# Jds-040-Usb-C.net
KiCad netlist of a schematic drawn in EAGLE
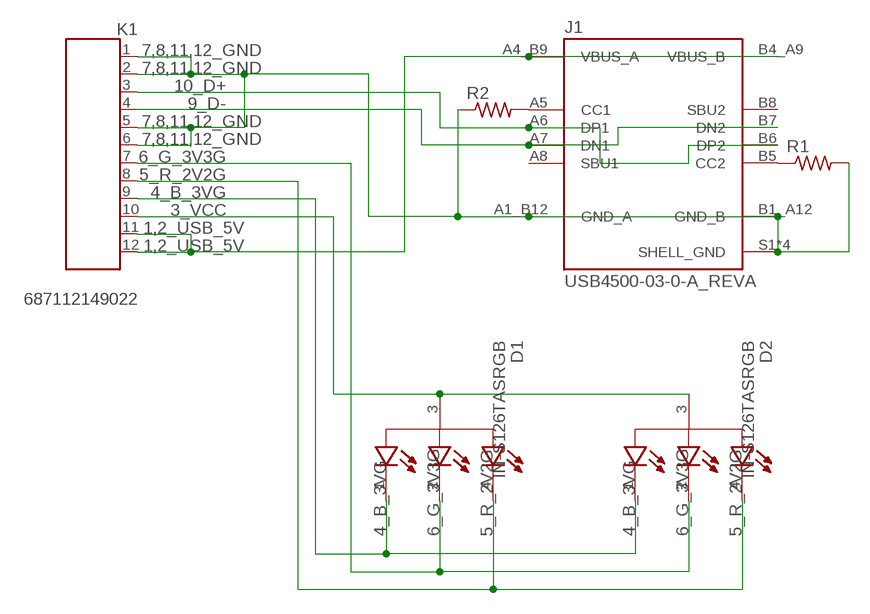
[diagram p0: schematic, sheet 1]

(export (version "E")
  (design (tool "Eeschema 10.0.6"))
  (components
    (comp (ref "D1")
      (value "IN-S126TASRGB")
      (footprint "eagle-import:LED_IN-S126TASRGB")
      (fields (field (name "MF") "Inolux"))
      (libsource (lib "eagle-import") (part "IN-S126TASRGB"))
    )
    (comp (ref "D2")
      (value "IN-S126TASRGB")
      (footprint "eagle-import:LED_IN-S126TASRGB")
      (fields (field (name "MF") "Inolux"))
      (libsource (lib "eagle-import") (part "IN-S126TASRGB"))
    )
    (comp (ref "J1")
      (value "USB4500-03-0-A_REVA")
      (footprint "eagle-import:GCT_USB4500-03-0-A_REVA")
      (fields (field (name "MF") "Global Connector Technology") (field (name "MP") "USB4500-03-0-A"))
      (libsource (lib "eagle-import") (part "USB4500-03-0-A_REVA"))
    )
    (comp (ref "K1")
      (value "687112149022")
      (footprint "eagle-import:687112149022")
      (libsource (lib "eagle-import") (part "687112149022"))
    )
    (comp (ref "R1")
      (value "5k1")
      (footprint "eagle-import:RES_0603")
      (fields
        (field (name "DIGIKEY_PART_NUMBER") "311-0.0GRTR-ND")
        (field (name "MANUFACTURER") "Yageo")
        (field (name "MPN") "RC0603JR-070RL")
        (field (name "CREATED_BY") "PCBLayout.com")
      )
      (libsource (lib "eagle-import") (part "RC0603JR-070RL"))
    )
    (comp (ref "R2")
      (value "5k1")
      (footprint "eagle-import:RES_0603")
      (fields
        (field (name "DIGIKEY_PART_NUMBER") "311-0.0GRTR-ND")
        (field (name "MANUFACTURER") "Yageo")
        (field (name "MPN") "RC0603JR-070RL")
        (field (name "CREATED_BY") "PCBLayout.com")
      )
      (libsource (lib "eagle-import") (part "RC0603JR-070RL"))
    )
  )
  (nets
    (net (code "1") (name "/1,2_USB_5V") (class "Default")
      (node (ref "J1") (pin "A4_B9") (pinfunction "VBUS_A_A4_B9") (pintype "power_in"))
      (node (ref "J1") (pin "B4_A9") (pinfunction "VBUS_B_B4_A9") (pintype "power_in"))
      (node (ref "K1") (pin "11") (pinfunction "11_11") (pintype "passive"))
      (node (ref "K1") (pin "12") (pinfunction "12_12") (pintype "passive"))
    )
    (net (code "2") (name "/3_VCC") (class "Default")
      (node (ref "D1") (pin "3") (pinfunction "COM+_3") (pintype "passive"))
      (node (ref "D2") (pin "3") (pinfunction "COM+_3") (pintype "passive"))
      (node (ref "K1") (pin "10") (pinfunction "10_10") (pintype "passive"))
    )
    (net (code "3") (name "/4_B_3VG") (class "Default")
      (node (ref "D1") (pin "1") (pinfunction "B_1") (pintype "passive"))
      (node (ref "D2") (pin "1") (pinfunction "B_1") (pintype "passive"))
      (node (ref "K1") (pin "9") (pinfunction "9_9") (pintype "passive"))
    )
    (net (code "4") (name "/5_R_2V2G") (class "Default")
      (node (ref "D1") (pin "4") (pinfunction "R_4") (pintype "passive"))
      (node (ref "D2") (pin "4") (pinfunction "R_4") (pintype "passive"))
      (node (ref "K1") (pin "8") (pinfunction "8_8") (pintype "passive"))
    )
    (net (code "5") (name "/6_G_3V3G") (class "Default")
      (node (ref "D1") (pin "2") (pinfunction "G_2") (pintype "passive"))
      (node (ref "D2") (pin "2") (pinfunction "G_2") (pintype "passive"))
      (node (ref "K1") (pin "7") (pinfunction "7_7") (pintype "passive"))
    )
    (net (code "6") (name "/7,8,11,12_GND") (class "Default")
      (node (ref "J1") (pin "A1_B12") (pinfunction "GND_A_A1_B12") (pintype "power_in"))
      (node (ref "J1") (pin "B1_A12") (pinfunction "GND_B_B1_A12") (pintype "power_in"))
      (node (ref "J1") (pin "S1") (pinfunction "SHELL_GND_S1") (pintype "power_in"))
      (node (ref "J1") (pin "S2") (pinfunction "SHELL_GND_S2") (pintype "power_in"))
      (node (ref "J1") (pin "S3") (pinfunction "SHELL_GND_S3") (pintype "power_in"))
      (node (ref "J1") (pin "S4") (pinfunction "SHELL_GND_S4") (pintype "power_in"))
      (node (ref "K1") (pin "1") (pinfunction "1_1") (pintype "passive"))
      (node (ref "K1") (pin "2") (pinfunction "2_2") (pintype "passive"))
      (node (ref "K1") (pin "5") (pinfunction "5_5") (pintype "passive"))
      (node (ref "K1") (pin "6") (pinfunction "6_6") (pintype "passive"))
      (node (ref "R1") (pin "2") (pinfunction "2_2") (pintype "passive"))
      (node (ref "R2") (pin "1") (pinfunction "1_1") (pintype "passive"))
    )
    (net (code "7") (name "/9_D-") (class "Default")
      (node (ref "J1") (pin "A7") (pinfunction "DN1_A7") (pintype "bidirectional"))
      (node (ref "J1") (pin "B7") (pinfunction "DN2_B7") (pintype "bidirectional"))
      (node (ref "K1") (pin "4") (pinfunction "4_4") (pintype "passive"))
    )
    (net (code "8") (name "/10_D+") (class "Default")
      (node (ref "J1") (pin "A6") (pinfunction "DP1_A6") (pintype "bidirectional"))
      (node (ref "J1") (pin "B6") (pinfunction "DP2_B6") (pintype "bidirectional"))
      (node (ref "K1") (pin "3") (pinfunction "3_3") (pintype "passive"))
    )
    (net (code "9") (name "Net-(J1-CC1)") (class "Default")
      (node (ref "J1") (pin "A5") (pinfunction "CC1_A5") (pintype "bidirectional"))
      (node (ref "R2") (pin "2") (pinfunction "2_2") (pintype "passive"))
    )
    (net (code "10") (name "Net-(J1-CC2)") (class "Default")
      (node (ref "J1") (pin "B5") (pinfunction "CC2_B5") (pintype "bidirectional"))
      (node (ref "R1") (pin "1") (pinfunction "1_1") (pintype "passive"))
    )
    (net (code "11") (name "unconnected-(J1-SBU1-PadA8)") (class "Default")
      (node (ref "J1") (pin "A8") (pinfunction "SBU1_A8") (pintype "bidirectional"))
    )
    (net (code "12") (name "unconnected-(J1-SBU2-PadB8)") (class "Default")
      (node (ref "J1") (pin "B8") (pinfunction "SBU2_B8") (pintype "bidirectional"))
    )
  )
)
